# HV_power.net
KiCad netlist of a schematic drawn in Altium Designer
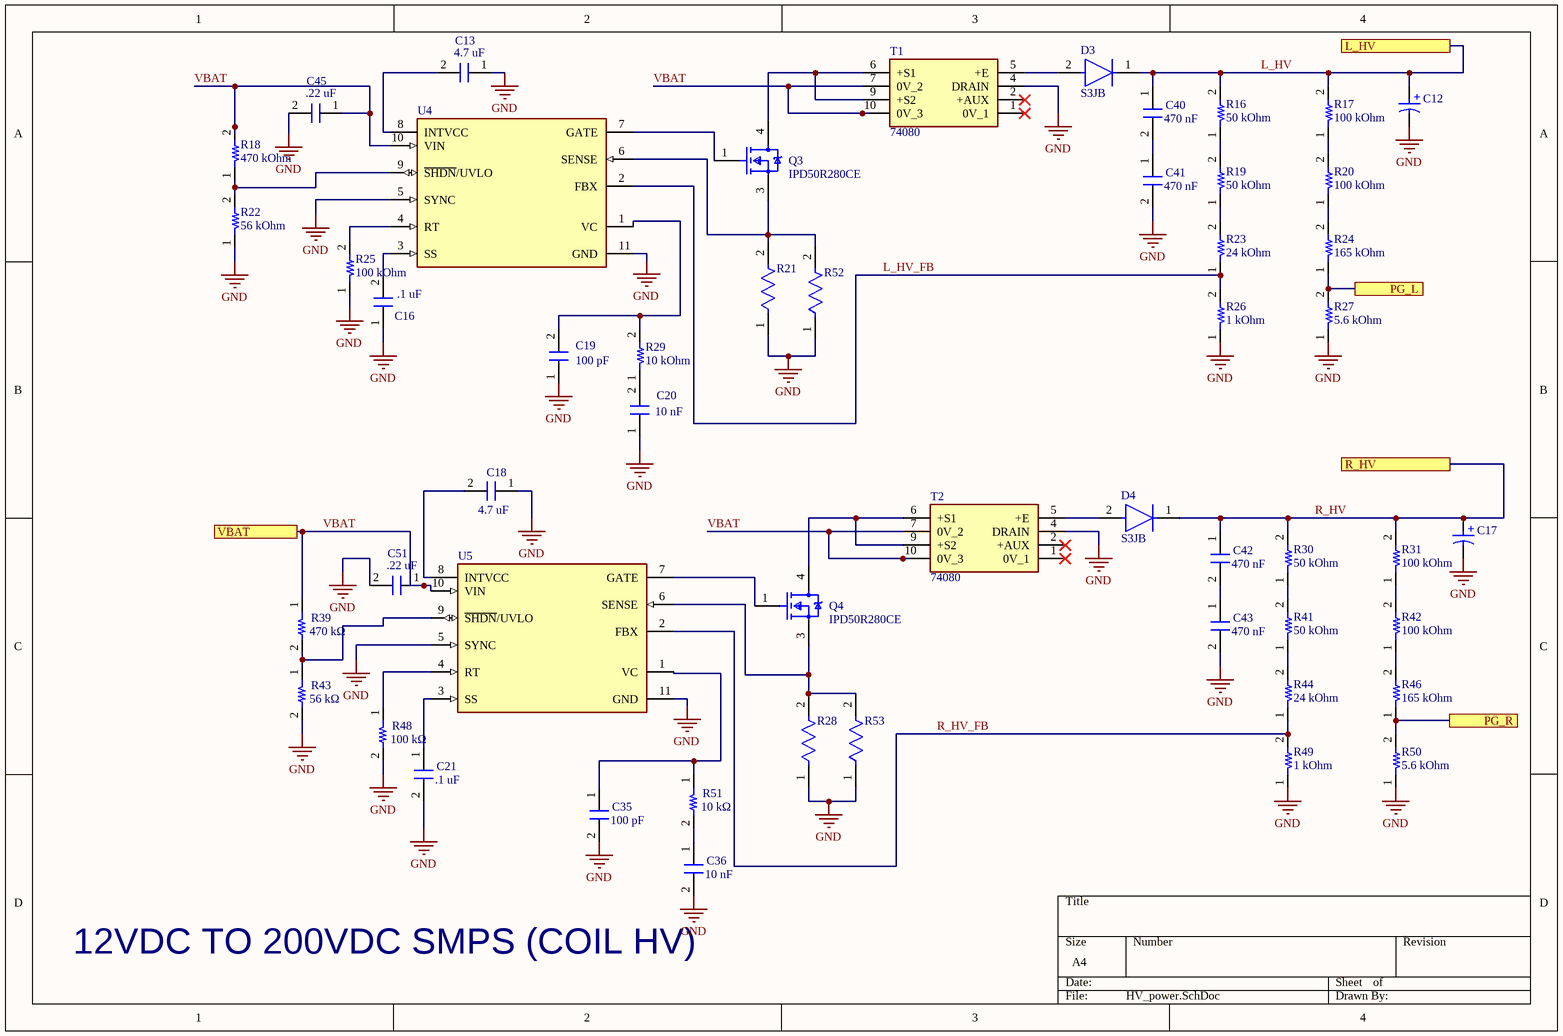
[diagram p0: HV_power.SchDoc]

(export (version "E")
  (design (tool "Eeschema 10.0.6"))
  (components
    (comp (ref "C12")
      (value "860021373001")
      (footprint "WCAP-ATG5_D6.3H11")
      (description "860021373001 WCAP-ATG5 Aluminum Electrolytic Capacitors")
      (fields (field (name "TOLERANCE") "20%"))
      (libsource (lib "Altium Content Vault") (part "Capacitor_Polarized"))
    )
    (comp (ref "C13")
      (value "4.7 uF")
      (footprint "0603_FP")
      (fields (field (name "Comment") "GRM21BR61C475KA88L"))
      (libsource (lib "RC_sch") (part "Capacitor_0603"))
    )
    (comp (ref "C16")
      (value ".1 uF")
      (footprint "0603_FP")
      (fields (field (name "Comment") "Capacitor_0603"))
      (libsource (lib "RC_sch") (part "Capacitor_0603"))
    )
    (comp (ref "C17")
      (value "860021373001")
      (footprint "WCAP-ATG5_D6.3H11")
      (description "860021373001 WCAP-ATG5 Aluminum Electrolytic Capacitors")
      (fields (field (name "TOLERANCE") "20%"))
      (libsource (lib "Altium Content Vault") (part "Capacitor_Polarized"))
    )
    (comp (ref "C18")
      (value "4.7 uF")
      (footprint "0603_FP")
      (fields (field (name "Comment") "Capacitor_0603"))
      (libsource (lib "RC_sch") (part "Capacitor_0603"))
    )
    (comp (ref "C19")
      (value "100 pF")
      (footprint "0603_FP")
      (fields (field (name "Comment") "Capacitor_0603"))
      (libsource (lib "RC_sch") (part "Capacitor_0603"))
    )
    (comp (ref "C20")
      (value "10 nF")
      (footprint "0603_FP")
      (fields (field (name "Comment") "Capacitor_0603"))
      (libsource (lib "RC_sch") (part "Capacitor_0603"))
    )
    (comp (ref "C21")
      (value ".1 uF")
      (footprint "0603_FP")
      (fields (field (name "Comment") "Capacitor_0603"))
      (libsource (lib "RC_sch") (part "Capacitor_0603"))
    )
    (comp (ref "C35")
      (value "100 pF")
      (footprint "0603_FP")
      (fields (field (name "Comment") "Capacitor_0603"))
      (libsource (lib "RC_sch") (part "Capacitor_0603"))
    )
    (comp (ref "C36")
      (value "10 nF")
      (footprint "0603_FP")
      (fields (field (name "Comment") "Capacitor_0603"))
      (libsource (lib "RC_sch") (part "Capacitor_0603"))
    )
    (comp (ref "C40")
      (value "470 nF")
      (footprint "0603_FP")
      (fields (field (name "Comment") "Capacitor_0603"))
      (libsource (lib "RC_sch") (part "Capacitor_0603"))
    )
    (comp (ref "C41")
      (value "470 nF")
      (footprint "0603_FP")
      (fields (field (name "Comment") "Capacitor_0603"))
      (libsource (lib "RC_sch") (part "Capacitor_0603"))
    )
    (comp (ref "C42")
      (value "470 nF")
      (footprint "0603_FP")
      (fields (field (name "Comment") "Capacitor_0603"))
      (libsource (lib "RC_sch") (part "Capacitor_0603"))
    )
    (comp (ref "C43")
      (value "470 nF")
      (footprint "0603_FP")
      (fields (field (name "Comment") "Capacitor_0603"))
      (libsource (lib "RC_sch") (part "Capacitor_0603"))
    )
    (comp (ref "C45")
      (value ".22 uF")
      (footprint "0603_FP")
      (fields (field (name "Comment") "GRM21BR61C475KA88L"))
      (libsource (lib "RC_sch") (part "Capacitor_0603"))
    )
    (comp (ref "C51")
      (value ".22 uF")
      (footprint "0603_FP")
      (fields (field (name "Comment") "GRM21BR61C475KA88L"))
      (libsource (lib "RC_sch") (part "Capacitor_0603"))
    )
    (comp (ref "D3")
      (value "S3JB")
      (footprint "FP-403AF-MFG")
      (description "S3JB Rectifier Diode, 1 Phase, 1 Element, 3A, 600V V(RRM), Silicon, DO-214AA")
      (libsource (lib "Altium Content Vault") (part "e8bb5000357cae87636711d27716c66"))
    )
    (comp (ref "D4")
      (value "S3JB")
      (footprint "FP-403AF-MFG")
      (description "S3JB Rectifier Diode, 1 Phase, 1 Element, 3A, 600V V(RRM), Silicon, DO-214AA")
      (libsource (lib "Altium Content Vault") (part "e8bb5000357cae87636711d27716c66"))
    )
    (comp (ref "Q3")
      (value "IPD50R280CE")
      (footprint "FP-PG-TO252-3-MFG")
      (description "MOSFET N-CH 30V 161A DPAK")
      (fields
        (field (name "OCTOPART") "https://octopart.com/irlr7843trpbf-infineon-65875062")
        (field (name "MANUFACTURER PART NUMBER") "IRLR7843TRPBF")
      )
      (libsource (lib "Altium Content Vault") (part "2f21c11e83d30f418bb422e5a3b3d11"))
    )
    (comp (ref "Q4")
      (value "IPD50R280CE")
      (footprint "FP-PG-TO252-3-MFG")
      (description "MOSFET N-CH 30V 161A DPAK")
      (fields
        (field (name "OCTOPART") "https://octopart.com/irlr7843trpbf-infineon-65875062")
        (field (name "MANUFACTURER PART NUMBER") "IRLR7843TRPBF")
      )
      (libsource (lib "Altium Content Vault") (part "2f21c11e83d30f418bb422e5a3b3d11"))
    )
    (comp (ref "R16")
      (value "50 kOhm")
      (footprint "0603_FP")
      (fields (field (name "Comment") "Resistor_0603"))
      (libsource (lib "RC_sch") (part "Resistor_0603"))
    )
    (comp (ref "R17")
      (value "100 kOhm")
      (footprint "0603_FP")
      (fields (field (name "Comment") "Resistor_0603"))
      (libsource (lib "RC_sch") (part "Resistor_0603"))
    )
    (comp (ref "R18")
      (value "470 kOhm")
      (footprint "0603_FP")
      (fields (field (name "Comment") "Resistor_0603"))
      (libsource (lib "RC_sch") (part "Resistor_0603"))
    )
    (comp (ref "R19")
      (value "50 kOhm")
      (footprint "0603_FP")
      (fields (field (name "Comment") "Resistor_0603"))
      (libsource (lib "RC_sch") (part "Resistor_0603"))
    )
    (comp (ref "R20")
      (value "100 kOhm")
      (footprint "0603_FP")
      (fields (field (name "Comment") "Resistor_0603"))
      (libsource (lib "RC_sch") (part "Resistor_0603"))
    )
    (comp (ref "R21")
      (value "CSRN2010FK20L0")
      (footprint "FP-CSRN2010-IPC_B")
      (description "Res Thick Film 2010 20mΩ 1% 1W ±250ppm/°C Molded SMD Plastic T/R")
      (fields (field (name "TOLERANCE") "1%"))
      (libsource (lib "Altium Content Vault") (part "1029c3af85768c4190bb7ad29bc67b5"))
    )
    (comp (ref "R22")
      (value "56 kOhm")
      (footprint "0603_FP")
      (fields (field (name "Comment") "Resistor_0603"))
      (libsource (lib "RC_sch") (part "Resistor_0603"))
    )
    (comp (ref "R23")
      (value "24 kOhm")
      (footprint "0603_FP")
      (fields (field (name "Comment") "Resistor_0603"))
      (libsource (lib "RC_sch") (part "Resistor_0603"))
    )
    (comp (ref "R24")
      (value "165 kOhm")
      (footprint "0603_FP")
      (fields (field (name "Comment") "Resistor_0603"))
      (libsource (lib "RC_sch") (part "Resistor_0603"))
    )
    (comp (ref "R25")
      (value "100 kOhm")
      (footprint "0603_FP")
      (fields (field (name "Comment") "Resistor_0603"))
      (libsource (lib "RC_sch") (part "Resistor_0603"))
    )
    (comp (ref "R26")
      (value "1 kOhm")
      (footprint "0603_FP")
      (fields (field (name "Comment") "Resistor_0603"))
      (libsource (lib "RC_sch") (part "Resistor_0603"))
    )
    (comp (ref "R27")
      (value "5.6 kOhm")
      (footprint "0603_FP")
      (fields (field (name "Comment") "Resistor_0603"))
      (libsource (lib "RC_sch") (part "Resistor_0603"))
    )
    (comp (ref "R28")
      (value "CSRN2010FK20L0")
      (footprint "FP-CSRN2010-IPC_B")
      (description "Res Thick Film 2010 20mΩ 1% 1W ±250ppm/°C Molded SMD Plastic T/R")
      (fields (field (name "TOLERANCE") "1%"))
      (libsource (lib "Altium Content Vault") (part "1029c3af85768c4190bb7ad29bc67b5"))
    )
    (comp (ref "R29")
      (value "10 kOhm")
      (footprint "0603_FP")
      (fields (field (name "Comment") "Resistor_0603"))
      (libsource (lib "RC_sch") (part "Resistor_0603"))
    )
    (comp (ref "R30")
      (value "50 kOhm")
      (footprint "0603_FP")
      (fields (field (name "Comment") "Resistor_0603"))
      (libsource (lib "RC_sch") (part "Resistor_0603"))
    )
    (comp (ref "R31")
      (value "100 kOhm")
      (footprint "0603_FP")
      (fields (field (name "Comment") "Resistor_0603"))
      (libsource (lib "RC_sch") (part "Resistor_0603"))
    )
    (comp (ref "R39")
      (value "470 kΩ")
      (footprint "0603_FP")
      (fields (field (name "Comment") "Resistor_0603"))
      (libsource (lib "RC_sch") (part "Resistor_0603"))
    )
    (comp (ref "R41")
      (value "50 kOhm")
      (footprint "0603_FP")
      (fields (field (name "Comment") "Resistor_0603"))
      (libsource (lib "RC_sch") (part "Resistor_0603"))
    )
    (comp (ref "R42")
      (value "100 kOhm")
      (footprint "0603_FP")
      (fields (field (name "Comment") "Resistor_0603"))
      (libsource (lib "RC_sch") (part "Resistor_0603"))
    )
    (comp (ref "R43")
      (value "56 kΩ")
      (footprint "0603_FP")
      (fields (field (name "Comment") "Resistor_0603"))
      (libsource (lib "RC_sch") (part "Resistor_0603"))
    )
    (comp (ref "R44")
      (value "24 kOhm")
      (footprint "0603_FP")
      (fields (field (name "Comment") "Resistor_0603"))
      (libsource (lib "RC_sch") (part "Resistor_0603"))
    )
    (comp (ref "R46")
      (value "165 kOhm")
      (footprint "0603_FP")
      (fields (field (name "Comment") "Resistor_0603"))
      (libsource (lib "RC_sch") (part "Resistor_0603"))
    )
    (comp (ref "R48")
      (value "100 kΩ")
      (footprint "0603_FP")
      (fields (field (name "Comment") "Resistor_0603"))
      (libsource (lib "RC_sch") (part "Resistor_0603"))
    )
    (comp (ref "R49")
      (value "1 kOhm")
      (footprint "0603_FP")
      (fields (field (name "Comment") "Resistor_0603"))
      (libsource (lib "RC_sch") (part "Resistor_0603"))
    )
    (comp (ref "R50")
      (value "5.6 kOhm")
      (footprint "0603_FP")
      (fields (field (name "Comment") "Resistor_0603"))
      (libsource (lib "RC_sch") (part "Resistor_0603"))
    )
    (comp (ref "R51")
      (value "10 kΩ")
      (footprint "0603_FP")
      (fields (field (name "Comment") "Resistor_0603"))
      (libsource (lib "RC_sch") (part "Resistor_0603"))
    )
    (comp (ref "R52")
      (value "CSRN2010FK20L0")
      (footprint "FP-CSRN2010-IPC_B")
      (description "Res Thick Film 2010 20mΩ 1% 1W ±250ppm/°C Molded SMD Plastic T/R")
      (fields (field (name "TOLERANCE") "1%"))
      (libsource (lib "Altium Content Vault") (part "1029c3af85768c4190bb7ad29bc67b5"))
    )
    (comp (ref "R53")
      (value "CSRN2010FK20L0")
      (footprint "FP-CSRN2010-IPC_B")
      (description "Res Thick Film 2010 20mΩ 1% 1W ±250ppm/°C Molded SMD Plastic T/R")
      (fields (field (name "TOLERANCE") "1%"))
      (libsource (lib "Altium Content Vault") (part "1029c3af85768c4190bb7ad29bc67b5"))
    )
    (comp (ref "T1")
      (value "74080")
      (footprint "SamacSys:74080")
      (description "Transformer")
      (libsource (lib "*") (part "74080"))
    )
    (comp (ref "T2")
      (value "74080")
      (footprint "SamacSys:74080")
      (description "Transformer")
      (libsource (lib "*") (part "74080"))
    )
    (comp (ref "U4")
      (value "LT3758EDD#PBF")
      (footprint "FP-DD-10-05-08-1699-IPC_B")
      (description "IC REG CTRLR MULT TOPOLOGY 10DFN")
      (libsource (lib "Altium Content Vault") (part "079e3863d39c5e5796f69dc810f510e"))
    )
    (comp (ref "U5")
      (value "LT3758EDD#PBF")
      (footprint "FP-DD-10-05-08-1699-IPC_B")
      (description "IC REG CTRLR MULT TOPOLOGY 10DFN")
      (libsource (lib "Altium Content Vault") (part "079e3863d39c5e5796f69dc810f510e"))
    )
  )
  (nets
    (net (code "1") (name "/L_HV") (class "Default")
      (node (ref "C12") (pin "1") (pinfunction "P_1") (pintype "passive"))
      (node (ref "C40") (pin "1") (pinfunction "1_1") (pintype "passive"))
      (node (ref "D3") (pin "1") (pinfunction "C_1") (pintype "passive"))
      (node (ref "R16") (pin "2") (pinfunction "2_2") (pintype "passive"))
      (node (ref "R17") (pin "2") (pinfunction "2_2") (pintype "passive"))
    )
    (net (code "2") (name "/L_HV_FB") (class "Default")
      (node (ref "R23") (pin "1") (pinfunction "1_1") (pintype "passive"))
      (node (ref "R26") (pin "2") (pinfunction "2_2") (pintype "passive"))
      (node (ref "U4") (pin "2") (pinfunction "FBX_2") (pintype "passive"))
    )
    (net (code "3") (name "/PG_L") (class "Default")
      (node (ref "R24") (pin "1") (pinfunction "1_1") (pintype "passive"))
      (node (ref "R27") (pin "2") (pinfunction "2_2") (pintype "passive"))
    )
    (net (code "4") (name "/PG_R") (class "Default")
      (node (ref "R46") (pin "1") (pinfunction "1_1") (pintype "passive"))
      (node (ref "R50") (pin "2") (pinfunction "2_2") (pintype "passive"))
    )
    (net (code "5") (name "/R_HV") (class "Default")
      (node (ref "C17") (pin "1") (pinfunction "P_1") (pintype "passive"))
      (node (ref "C42") (pin "1") (pinfunction "1_1") (pintype "passive"))
      (node (ref "D4") (pin "1") (pinfunction "C_1") (pintype "passive"))
      (node (ref "R30") (pin "2") (pinfunction "2_2") (pintype "passive"))
      (node (ref "R31") (pin "2") (pinfunction "2_2") (pintype "passive"))
    )
    (net (code "6") (name "/R_HV_FB") (class "Default")
      (node (ref "R44") (pin "1") (pinfunction "1_1") (pintype "passive"))
      (node (ref "R49") (pin "2") (pinfunction "2_2") (pintype "passive"))
      (node (ref "U5") (pin "2") (pinfunction "FBX_2") (pintype "passive"))
    )
    (net (code "7") (name "/VBAT") (class "Default")
      (node (ref "C45") (pin "1") (pinfunction "1_1") (pintype "passive"))
      (node (ref "C51") (pin "1") (pinfunction "1_1") (pintype "passive"))
      (node (ref "R18") (pin "2") (pinfunction "2_2") (pintype "passive"))
      (node (ref "R39") (pin "1") (pinfunction "1_1") (pintype "passive"))
      (node (ref "T1") (pin "10") (pinfunction "0V_3_10") (pintype "passive"))
      (node (ref "T1") (pin "7") (pinfunction "0V_2_7") (pintype "passive"))
      (node (ref "T2") (pin "10") (pinfunction "0V_3_10") (pintype "passive"))
      (node (ref "T2") (pin "7") (pinfunction "0V_2_7") (pintype "passive"))
      (node (ref "U4") (pin "10") (pinfunction "VIN_10") (pintype "input"))
      (node (ref "U5") (pin "10") (pinfunction "VIN_10") (pintype "input"))
    )
    (net (code "8") (name "GND") (class "Default")
      (node (ref "C12") (pin "2") (pinfunction "N_2") (pintype "passive"))
      (node (ref "C13") (pin "1") (pinfunction "1_1") (pintype "passive"))
      (node (ref "C16") (pin "1") (pinfunction "1_1") (pintype "passive"))
      (node (ref "C17") (pin "2") (pinfunction "N_2") (pintype "passive"))
      (node (ref "C18") (pin "1") (pinfunction "1_1") (pintype "passive"))
      (node (ref "C19") (pin "1") (pinfunction "1_1") (pintype "passive"))
      (node (ref "C20") (pin "1") (pinfunction "1_1") (pintype "passive"))
      (node (ref "C21") (pin "2") (pinfunction "2_2") (pintype "passive"))
      (node (ref "C35") (pin "2") (pinfunction "2_2") (pintype "passive"))
      (node (ref "C36") (pin "2") (pinfunction "2_2") (pintype "passive"))
      (node (ref "C41") (pin "2") (pinfunction "2_2") (pintype "passive"))
      (node (ref "C43") (pin "2") (pinfunction "2_2") (pintype "passive"))
      (node (ref "C45") (pin "2") (pinfunction "2_2") (pintype "passive"))
      (node (ref "C51") (pin "2") (pinfunction "2_2") (pintype "passive"))
      (node (ref "R21") (pin "1") (pinfunction "1_1") (pintype "passive"))
      (node (ref "R22") (pin "1") (pinfunction "1_1") (pintype "passive"))
      (node (ref "R25") (pin "1") (pinfunction "1_1") (pintype "passive"))
      (node (ref "R26") (pin "1") (pinfunction "1_1") (pintype "passive"))
      (node (ref "R27") (pin "1") (pinfunction "1_1") (pintype "passive"))
      (node (ref "R28") (pin "1") (pinfunction "1_1") (pintype "passive"))
      (node (ref "R43") (pin "2") (pinfunction "2_2") (pintype "passive"))
      (node (ref "R48") (pin "2") (pinfunction "2_2") (pintype "passive"))
      (node (ref "R49") (pin "1") (pinfunction "1_1") (pintype "passive"))
      (node (ref "R50") (pin "1") (pinfunction "1_1") (pintype "passive"))
      (node (ref "R52") (pin "1") (pinfunction "1_1") (pintype "passive"))
      (node (ref "R53") (pin "1") (pinfunction "1_1") (pintype "passive"))
      (node (ref "T1") (pin "4") (pinfunction "DRAIN_4") (pintype "passive"))
      (node (ref "T2") (pin "4") (pinfunction "DRAIN_4") (pintype "passive"))
      (node (ref "U4") (pin "11") (pinfunction "GND_11") (pintype "power_in"))
      (node (ref "U4") (pin "5") (pinfunction "SYNC_5") (pintype "input"))
      (node (ref "U5") (pin "11") (pinfunction "GND_11") (pintype "power_in"))
      (node (ref "U5") (pin "5") (pinfunction "SYNC_5") (pintype "input"))
    )
    (net (code "9") (name "Net-(C20-Pad2)") (class "Default")
      (node (ref "C20") (pin "2") (pinfunction "2_2") (pintype "passive"))
      (node (ref "R29") (pin "1") (pinfunction "1_1") (pintype "passive"))
    )
    (net (code "10") (name "Net-(C36-Pad1)") (class "Default")
      (node (ref "C36") (pin "1") (pinfunction "1_1") (pintype "passive"))
      (node (ref "R51") (pin "2") (pinfunction "2_2") (pintype "passive"))
    )
    (net (code "11") (name "Net-(C40-Pad2)") (class "Default")
      (node (ref "C40") (pin "2") (pinfunction "2_2") (pintype "passive"))
      (node (ref "C41") (pin "1") (pinfunction "1_1") (pintype "passive"))
    )
    (net (code "12") (name "Net-(C42-Pad2)") (class "Default")
      (node (ref "C42") (pin "2") (pinfunction "2_2") (pintype "passive"))
      (node (ref "C43") (pin "1") (pinfunction "1_1") (pintype "passive"))
    )
    (net (code "13") (name "Net-(D3-A)") (class "Default")
      (node (ref "D3") (pin "2") (pinfunction "A_2") (pintype "passive"))
      (node (ref "T1") (pin "5") (pinfunction "+E_5") (pintype "passive"))
    )
    (net (code "14") (name "Net-(D4-A)") (class "Default")
      (node (ref "D4") (pin "2") (pinfunction "A_2") (pintype "passive"))
      (node (ref "T2") (pin "5") (pinfunction "+E_5") (pintype "passive"))
    )
    (net (code "15") (name "Net-(Q3-DRAIN)") (class "Default")
      (node (ref "Q3") (pin "4") (pinfunction "DRAIN_4") (pintype "passive"))
      (node (ref "T1") (pin "6") (pinfunction "+S1_6") (pintype "passive"))
      (node (ref "T1") (pin "9") (pinfunction "+S2_9") (pintype "passive"))
    )
    (net (code "16") (name "Net-(Q3-GATE)") (class "Default")
      (node (ref "Q3") (pin "1") (pinfunction "GATE_1") (pintype "passive"))
      (node (ref "U4") (pin "7") (pinfunction "GATE_7") (pintype "passive"))
    )
    (net (code "17") (name "Net-(Q3-SOURCE)") (class "Default")
      (node (ref "Q3") (pin "3") (pinfunction "SOURCE_3") (pintype "passive"))
      (node (ref "R21") (pin "2") (pinfunction "2_2") (pintype "passive"))
      (node (ref "R52") (pin "2") (pinfunction "2_2") (pintype "passive"))
      (node (ref "U4") (pin "6") (pinfunction "SENSE_6") (pintype "input"))
    )
    (net (code "18") (name "Net-(Q4-DRAIN)") (class "Default")
      (node (ref "Q4") (pin "4") (pinfunction "DRAIN_4") (pintype "passive"))
      (node (ref "T2") (pin "6") (pinfunction "+S1_6") (pintype "passive"))
      (node (ref "T2") (pin "9") (pinfunction "+S2_9") (pintype "passive"))
    )
    (net (code "19") (name "Net-(Q4-GATE)") (class "Default")
      (node (ref "Q4") (pin "1") (pinfunction "GATE_1") (pintype "passive"))
      (node (ref "U5") (pin "7") (pinfunction "GATE_7") (pintype "passive"))
    )
    (net (code "20") (name "Net-(Q4-SOURCE)") (class "Default")
      (node (ref "Q4") (pin "3") (pinfunction "SOURCE_3") (pintype "passive"))
      (node (ref "R28") (pin "2") (pinfunction "2_2") (pintype "passive"))
      (node (ref "R53") (pin "2") (pinfunction "2_2") (pintype "passive"))
      (node (ref "U5") (pin "6") (pinfunction "SENSE_6") (pintype "input"))
    )
    (net (code "21") (name "Net-(R16-Pad1)") (class "Default")
      (node (ref "R16") (pin "1") (pinfunction "1_1") (pintype "passive"))
      (node (ref "R19") (pin "2") (pinfunction "2_2") (pintype "passive"))
    )
    (net (code "22") (name "Net-(R17-Pad1)") (class "Default")
      (node (ref "R17") (pin "1") (pinfunction "1_1") (pintype "passive"))
      (node (ref "R20") (pin "2") (pinfunction "2_2") (pintype "passive"))
    )
    (net (code "23") (name "Net-(R19-Pad1)") (class "Default")
      (node (ref "R19") (pin "1") (pinfunction "1_1") (pintype "passive"))
      (node (ref "R23") (pin "2") (pinfunction "2_2") (pintype "passive"))
    )
    (net (code "24") (name "Net-(R20-Pad1)") (class "Default")
      (node (ref "R20") (pin "1") (pinfunction "1_1") (pintype "passive"))
      (node (ref "R24") (pin "2") (pinfunction "2_2") (pintype "passive"))
    )
    (net (code "25") (name "Net-(R30-Pad1)") (class "Default")
      (node (ref "R30") (pin "1") (pinfunction "1_1") (pintype "passive"))
      (node (ref "R41") (pin "2") (pinfunction "2_2") (pintype "passive"))
    )
    (net (code "26") (name "Net-(R31-Pad1)") (class "Default")
      (node (ref "R31") (pin "1") (pinfunction "1_1") (pintype "passive"))
      (node (ref "R42") (pin "2") (pinfunction "2_2") (pintype "passive"))
    )
    (net (code "27") (name "Net-(R41-Pad1)") (class "Default")
      (node (ref "R41") (pin "1") (pinfunction "1_1") (pintype "passive"))
      (node (ref "R44") (pin "2") (pinfunction "2_2") (pintype "passive"))
    )
    (net (code "28") (name "Net-(R42-Pad1)") (class "Default")
      (node (ref "R42") (pin "1") (pinfunction "1_1") (pintype "passive"))
      (node (ref "R46") (pin "2") (pinfunction "2_2") (pintype "passive"))
    )
    (net (code "29") (name "Net-(U4-INTVCC)") (class "Default")
      (node (ref "C13") (pin "2") (pinfunction "2_2") (pintype "passive"))
      (node (ref "U4") (pin "8") (pinfunction "INTVCC_8") (pintype "power_in"))
    )
    (net (code "30") (name "Net-(U4-RT)") (class "Default")
      (node (ref "R25") (pin "2") (pinfunction "2_2") (pintype "passive"))
      (node (ref "U4") (pin "4") (pinfunction "RT_4") (pintype "input"))
    )
    (net (code "31") (name "Net-(U4-SS)") (class "Default")
      (node (ref "C16") (pin "2") (pinfunction "2_2") (pintype "passive"))
      (node (ref "U4") (pin "3") (pinfunction "SS_3") (pintype "input"))
    )
    (net (code "32") (name "Net-(U4-VC)") (class "Default")
      (node (ref "C19") (pin "2") (pinfunction "2_2") (pintype "passive"))
      (node (ref "R29") (pin "2") (pinfunction "2_2") (pintype "passive"))
      (node (ref "U4") (pin "1") (pinfunction "VC_1") (pintype "passive"))
    )
    (net (code "33") (name "Net-(U4-~{SHDN}{slash}UVLO)") (class "Default")
      (node (ref "R18") (pin "1") (pinfunction "1_1") (pintype "passive"))
      (node (ref "R22") (pin "2") (pinfunction "2_2") (pintype "passive"))
      (node (ref "U4") (pin "9") (pinfunction "~{SHDN}/UVLO_9") (pintype "bidirectional"))
    )
    (net (code "34") (name "Net-(U5-INTVCC)") (class "Default")
      (node (ref "C18") (pin "2") (pinfunction "2_2") (pintype "passive"))
      (node (ref "U5") (pin "8") (pinfunction "INTVCC_8") (pintype "power_in"))
    )
    (net (code "35") (name "Net-(U5-RT)") (class "Default")
      (node (ref "R48") (pin "1") (pinfunction "1_1") (pintype "passive"))
      (node (ref "U5") (pin "4") (pinfunction "RT_4") (pintype "input"))
    )
    (net (code "36") (name "Net-(U5-SS)") (class "Default")
      (node (ref "C21") (pin "1") (pinfunction "1_1") (pintype "passive"))
      (node (ref "U5") (pin "3") (pinfunction "SS_3") (pintype "input"))
    )
    (net (code "37") (name "Net-(U5-VC)") (class "Default")
      (node (ref "C35") (pin "1") (pinfunction "1_1") (pintype "passive"))
      (node (ref "R51") (pin "1") (pinfunction "1_1") (pintype "passive"))
      (node (ref "U5") (pin "1") (pinfunction "VC_1") (pintype "passive"))
    )
    (net (code "38") (name "Net-(U5-~{SHDN}{slash}UVLO)") (class "Default")
      (node (ref "R39") (pin "2") (pinfunction "2_2") (pintype "passive"))
      (node (ref "R43") (pin "1") (pinfunction "1_1") (pintype "passive"))
      (node (ref "U5") (pin "9") (pinfunction "~{SHDN}/UVLO_9") (pintype "bidirectional"))
    )
    (net (code "39") (name "unconnected-(T1-+AUX-Pad2)") (class "Default")
      (node (ref "T1") (pin "2") (pinfunction "+AUX_2") (pintype "passive+no_connect"))
    )
    (net (code "40") (name "unconnected-(T1-0V_1-Pad1)") (class "Default")
      (node (ref "T1") (pin "1") (pinfunction "0V_1_1") (pintype "passive+no_connect"))
    )
    (net (code "41") (name "unconnected-(T2-+AUX-Pad2)") (class "Default")
      (node (ref "T2") (pin "2") (pinfunction "+AUX_2") (pintype "passive+no_connect"))
    )
    (net (code "42") (name "unconnected-(T2-0V_1-Pad1)") (class "Default")
      (node (ref "T2") (pin "1") (pinfunction "0V_1_1") (pintype "passive+no_connect"))
    )
  )
)
